# Randys_Gut.net
KiCad netlist of a schematic drawn in EAGLE
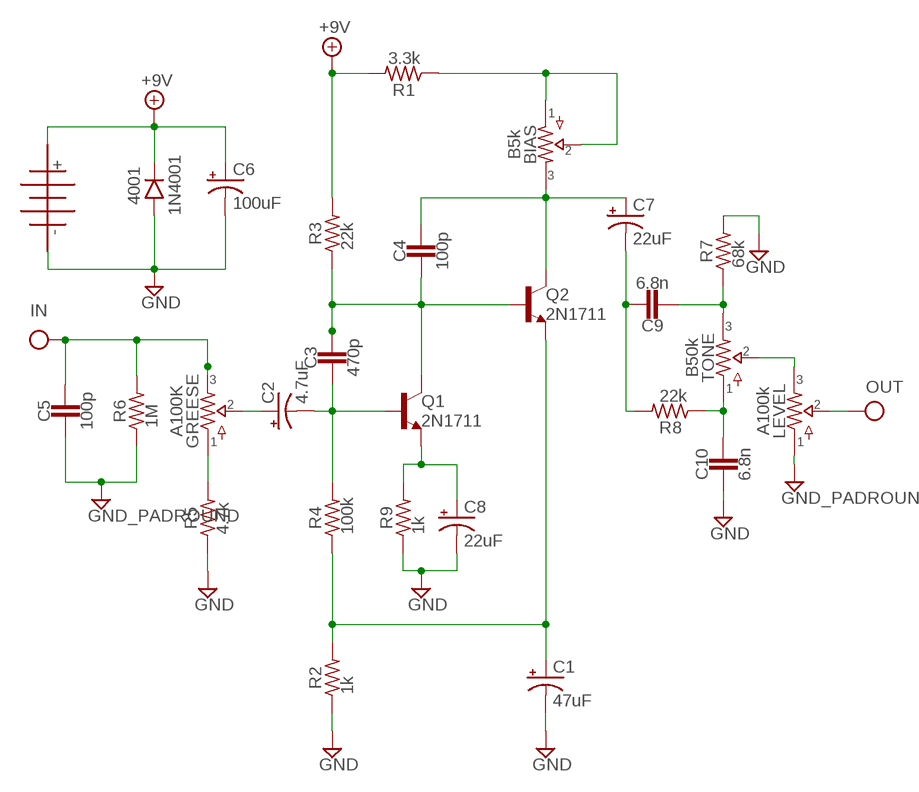
[diagram p0: schematic, sheet 1]

(export (version "E")
  (design (tool "Eeschema 10.0.6"))
  (components
    (comp (ref "4001")
      (value "1N4001")
      (footprint "eagle-import:DO41-3")
      (libsource (lib "eagle-import") (part "DO41.3"))
    )
    (comp (ref "BIAS")
      (value "B5k")
      (footprint "eagle-import:16MM_B.MOUNT")
      (libsource (lib "eagle-import") (part "16MM.1"))
    )
    (comp (ref "C1")
      (value "47uF")
      (footprint "eagle-import:063_025")
      (libsource (lib "eagle-import") (part "0631"))
    )
    (comp (ref "C2")
      (value "4.7uF")
      (footprint "eagle-import:050_020_1")
      (libsource (lib "eagle-import") (part "0501"))
    )
    (comp (ref "C3")
      (value "470p")
      (footprint "eagle-import:0.2_.SML")
      (libsource (lib "eagle-import") (part "CAP.2"))
    )
    (comp (ref "C4")
      (value "100p")
      (footprint "eagle-import:0.2_.SML")
      (libsource (lib "eagle-import") (part "CAP.2"))
    )
    (comp (ref "C5")
      (value "100p")
      (footprint "eagle-import:0.2_.SML")
      (libsource (lib "eagle-import") (part "CAP.2"))
    )
    (comp (ref "C6")
      (value "100uF")
      (footprint "eagle-import:063_025")
      (libsource (lib "eagle-import") (part "0631"))
    )
    (comp (ref "C7")
      (value "22uF")
      (footprint "eagle-import:050_020_1")
      (libsource (lib "eagle-import") (part "0501"))
    )
    (comp (ref "C8")
      (value "22uF")
      (footprint "eagle-import:050_020_1")
      (libsource (lib "eagle-import") (part "0501"))
    )
    (comp (ref "C9")
      (value "6.8n")
      (footprint "eagle-import:0.2_.SML")
      (libsource (lib "eagle-import") (part "CAP.2"))
    )
    (comp (ref "C10")
      (value "6.8n")
      (footprint "eagle-import:0.2_.SML")
      (libsource (lib "eagle-import") (part "CAP.2"))
    )
    (comp (ref "GI")
      (value "GND_PADROUND")
      (footprint "eagle-import:ROUND")
      (libsource (lib "eagle-import") (part "GND_PADROUND"))
    )
    (comp (ref "GO")
      (value "GND_PADROUND")
      (footprint "eagle-import:ROUND")
      (libsource (lib "eagle-import") (part "GND_PADROUND"))
    )
    (comp (ref "GREESE")
      (value "A100K")
      (footprint "eagle-import:16MM_B.MOUNT")
      (libsource (lib "eagle-import") (part "16MM.1"))
    )
    (comp (ref "IN")
      (value "IN")
      (footprint "eagle-import:SQUARE")
      (libsource (lib "eagle-import") (part "IN"))
    )
    (comp (ref "LEVEL")
      (value "A100k")
      (footprint "eagle-import:16MM_B.MOUNT")
      (libsource (lib "eagle-import") (part "16MM.1"))
    )
    (comp (ref "OUT")
      (value "OUT")
      (footprint "eagle-import:SQUARE")
      (libsource (lib "eagle-import") (part "OUT"))
    )
    (comp (ref "PWR")
      (value "BATTERYBAT2")
      (footprint "eagle-import:BATTERY2")
      (libsource (lib "eagle-import") (part "BATTERYBAT2"))
    )
    (comp (ref "Q1")
      (value "2N1711")
      (footprint "eagle-import:TO18")
      (libsource (lib "eagle-import") (part "2N2222A"))
    )
    (comp (ref "Q2")
      (value "2N1711")
      (footprint "eagle-import:TO18")
      (libsource (lib "eagle-import") (part "2N2222A"))
    )
    (comp (ref "R1")
      (value "3.3k")
      (footprint "eagle-import:R0207_3")
      (libsource (lib "eagle-import") (part "resistors_values_RESISTORS.3B"))
    )
    (comp (ref "R2")
      (value "1k")
      (footprint "eagle-import:R0207_3")
      (libsource (lib "eagle-import") (part "resistors_values_RESISTORS.3B"))
    )
    (comp (ref "R3")
      (value "22k")
      (footprint "eagle-import:R0207_3")
      (libsource (lib "eagle-import") (part "RESISTORS.3B"))
    )
    (comp (ref "R4")
      (value "100k")
      (footprint "eagle-import:R0207_3")
      (libsource (lib "eagle-import") (part "RESISTORS.3B"))
    )
    (comp (ref "R5")
      (value "4.7k")
      (footprint "eagle-import:R0207_3")
      (libsource (lib "eagle-import") (part "RESISTORS.3B"))
    )
    (comp (ref "R6")
      (value "1M")
      (footprint "eagle-import:R0207_3")
      (libsource (lib "eagle-import") (part "resistors_values_RESISTORS.3B"))
    )
    (comp (ref "R7")
      (value "68k")
      (footprint "eagle-import:R0207_3")
      (libsource (lib "eagle-import") (part "RESISTORS.3B"))
    )
    (comp (ref "R8")
      (value "22k")
      (footprint "eagle-import:R0207_3")
      (libsource (lib "eagle-import") (part "RESISTORS.3B"))
    )
    (comp (ref "R9")
      (value "1k")
      (footprint "eagle-import:R0207_3")
      (libsource (lib "eagle-import") (part "RESISTORS.3B"))
    )
    (comp (ref "TONE")
      (value "B50k")
      (footprint "eagle-import:16MM_B.MOUNT")
      (libsource (lib "eagle-import") (part "16MM.1"))
    )
  )
  (nets
    (net (code "1") (name "+9V") (class "Default")
      (node (ref "4001") (pin "C") (pinfunction "C_C") (pintype "passive"))
      (node (ref "C6") (pin "+") (pinfunction "+_+") (pintype "passive"))
      (node (ref "PWR") (pin "P$1") (pinfunction "P$1_P$1") (pintype "bidirectional"))
      (node (ref "R1") (pin "2") (pinfunction "2_2") (pintype "passive"))
      (node (ref "R3") (pin "2") (pinfunction "2_2") (pintype "passive"))
    )
    (net (code "2") (name "GND") (class "Default")
      (node (ref "4001") (pin "A") (pinfunction "A_A") (pintype "passive"))
      (node (ref "C1") (pin "-") (pinfunction "-_-") (pintype "passive"))
      (node (ref "C10") (pin "2") (pinfunction "2_2") (pintype "passive"))
      (node (ref "C5") (pin "2") (pinfunction "2_2") (pintype "passive"))
      (node (ref "C6") (pin "-") (pinfunction "-_-") (pintype "passive"))
      (node (ref "C8") (pin "-") (pinfunction "-_-") (pintype "passive"))
      (node (ref "GI") (pin "1") (pinfunction "GND_1") (pintype "power_in"))
      (node (ref "GO") (pin "1") (pinfunction "GND_1") (pintype "power_in"))
      (node (ref "LEVEL") (pin "1") (pinfunction "1_1") (pintype "passive"))
      (node (ref "PWR") (pin "P$2") (pinfunction "P$2_P$2") (pintype "bidirectional"))
      (node (ref "R2") (pin "1") (pinfunction "1_1") (pintype "passive"))
      (node (ref "R5") (pin "1") (pinfunction "1_1") (pintype "passive"))
      (node (ref "R6") (pin "1") (pinfunction "1_1") (pintype "passive"))
      (node (ref "R7") (pin "2") (pinfunction "2_2") (pintype "passive"))
      (node (ref "R9") (pin "1") (pinfunction "1_1") (pintype "passive"))
    )
    (net (code "3") (name "IN") (class "Default")
      (node (ref "C5") (pin "1") (pinfunction "1_1") (pintype "passive"))
      (node (ref "GREESE") (pin "3") (pinfunction "3_3") (pintype "passive"))
      (node (ref "IN") (pin "1") (pinfunction "IN_1") (pintype "power_in"))
      (node (ref "R6") (pin "2") (pinfunction "2_2") (pintype "passive"))
    )
    (net (code "4") (name "Net-(BIAS-Pad1)") (class "Default")
      (node (ref "BIAS") (pin "1") (pinfunction "1_1") (pintype "passive"))
      (node (ref "BIAS") (pin "2") (pinfunction "2_2") (pintype "passive"))
      (node (ref "R1") (pin "1") (pinfunction "1_1") (pintype "passive"))
    )
    (net (code "5") (name "Net-(C2-Pad+)") (class "Default")
      (node (ref "C2") (pin "+") (pinfunction "+_+") (pintype "passive"))
      (node (ref "GREESE") (pin "2") (pinfunction "2_2") (pintype "passive"))
    )
    (net (code "6") (name "Net-(C7-Pad-)") (class "Default")
      (node (ref "C7") (pin "-") (pinfunction "-_-") (pintype "passive"))
      (node (ref "C9") (pin "1") (pinfunction "1_1") (pintype "passive"))
      (node (ref "R8") (pin "2") (pinfunction "2_2") (pintype "passive"))
    )
    (net (code "7") (name "Net-(C9-Pad2)") (class "Default")
      (node (ref "C9") (pin "2") (pinfunction "2_2") (pintype "passive"))
      (node (ref "R7") (pin "1") (pinfunction "1_1") (pintype "passive"))
      (node (ref "TONE") (pin "3") (pinfunction "3_3") (pintype "passive"))
    )
    (net (code "8") (name "Net-(C10-Pad1)") (class "Default")
      (node (ref "C10") (pin "1") (pinfunction "1_1") (pintype "passive"))
      (node (ref "R8") (pin "1") (pinfunction "1_1") (pintype "passive"))
      (node (ref "TONE") (pin "1") (pinfunction "1_1") (pintype "passive"))
    )
    (net (code "9") (name "Net-(GREESE-Pad1)") (class "Default")
      (node (ref "GREESE") (pin "1") (pinfunction "1_1") (pintype "passive"))
      (node (ref "R5") (pin "2") (pinfunction "2_2") (pintype "passive"))
    )
    (net (code "10") (name "Net-(LEVEL-Pad3)") (class "Default")
      (node (ref "LEVEL") (pin "3") (pinfunction "3_3") (pintype "passive"))
      (node (ref "TONE") (pin "2") (pinfunction "2_2") (pintype "passive"))
    )
    (net (code "11") (name "Net-(Q1-B)") (class "Default")
      (node (ref "C2") (pin "-") (pinfunction "-_-") (pintype "passive"))
      (node (ref "C3") (pin "2") (pinfunction "2_2") (pintype "passive"))
      (node (ref "Q1") (pin "2") (pinfunction "B_2") (pintype "passive"))
      (node (ref "R4") (pin "2") (pinfunction "2_2") (pintype "passive"))
    )
    (net (code "12") (name "Net-(Q1-C)") (class "Default")
      (node (ref "C3") (pin "1") (pinfunction "1_1") (pintype "passive"))
      (node (ref "C4") (pin "2") (pinfunction "2_2") (pintype "passive"))
      (node (ref "Q1") (pin "3") (pinfunction "C_3") (pintype "passive"))
      (node (ref "Q2") (pin "2") (pinfunction "B_2") (pintype "passive"))
      (node (ref "R3") (pin "1") (pinfunction "1_1") (pintype "passive"))
    )
    (net (code "13") (name "Net-(Q1-E)") (class "Default")
      (node (ref "C8") (pin "+") (pinfunction "+_+") (pintype "passive"))
      (node (ref "Q1") (pin "1") (pinfunction "E_1") (pintype "passive"))
      (node (ref "R9") (pin "2") (pinfunction "2_2") (pintype "passive"))
    )
    (net (code "14") (name "Net-(Q2-C)") (class "Default")
      (node (ref "BIAS") (pin "3") (pinfunction "3_3") (pintype "passive"))
      (node (ref "C4") (pin "1") (pinfunction "1_1") (pintype "passive"))
      (node (ref "C7") (pin "+") (pinfunction "+_+") (pintype "passive"))
      (node (ref "Q2") (pin "3") (pinfunction "C_3") (pintype "passive"))
    )
    (net (code "15") (name "Net-(Q2-E)") (class "Default")
      (node (ref "C1") (pin "+") (pinfunction "+_+") (pintype "passive"))
      (node (ref "Q2") (pin "1") (pinfunction "E_1") (pintype "passive"))
      (node (ref "R2") (pin "2") (pinfunction "2_2") (pintype "passive"))
      (node (ref "R4") (pin "1") (pinfunction "1_1") (pintype "passive"))
    )
    (net (code "16") (name "OUT") (class "Default")
      (node (ref "LEVEL") (pin "2") (pinfunction "2_2") (pintype "passive"))
      (node (ref "OUT") (pin "1") (pinfunction "OUT_1") (pintype "power_in"))
    )
  )
)
